# numitron_clock.net
KiCad netlist of a schematic drawn in EAGLE
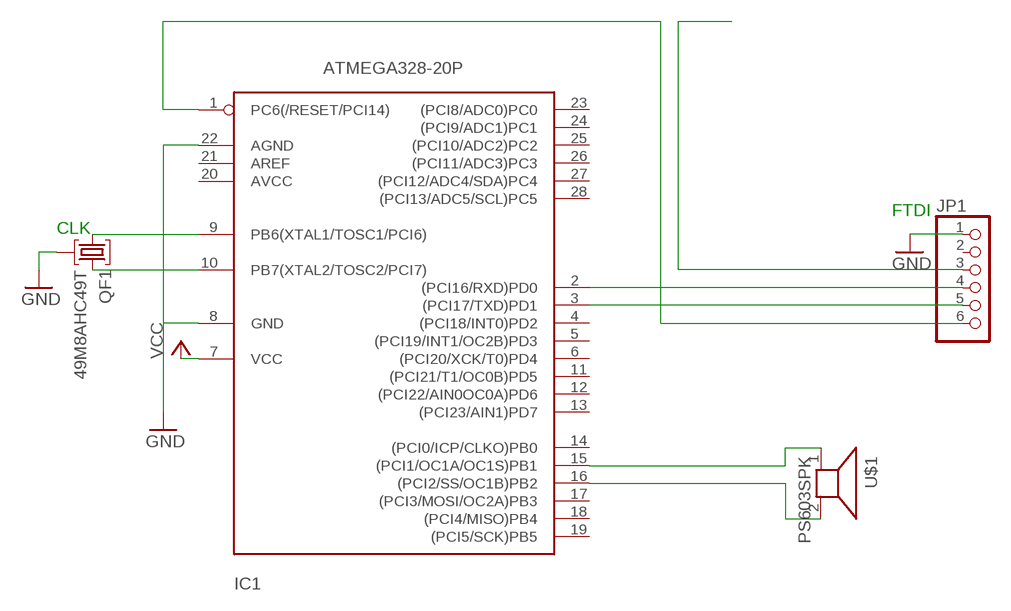
[diagram p0: schematic, sheet 1]

(export (version "E")
  (design (tool "Eeschema 10.0.6"))
  (components
    (comp (ref "IC1")
      (value "ATMEGA328-20P")
      (footprint "eagle-import:DIL28-3")
      (libsource (lib "eagle-import") (part "ATMEGA328P-20"))
    )
    (comp (ref "JP1")
      (value "PINHD-1X6")
      (footprint "eagle-import:1X06")
      (libsource (lib "eagle-import") (part "PINHD-1X6"))
    )
    (comp (ref "QF1")
      (value "49M8AHC49T")
      (footprint "eagle-import:HC49U")
      (libsource (lib "eagle-import") (part "49M8AHC49T"))
    )
    (comp (ref "U$1")
      (value "PS603SPK")
      (footprint "eagle-import:PS603")
      (libsource (lib "eagle-import") (part "PS603SPK"))
    )
  )
  (nets
    (net (code "1") (name "GND") (class "Default")
      (node (ref "IC1") (pin "22") (pinfunction "AGND_22") (pintype "bidirectional"))
      (node (ref "IC1") (pin "8") (pinfunction "GND_8") (pintype "bidirectional"))
      (node (ref "JP1") (pin "1") (pinfunction "1_1") (pintype "passive"))
      (node (ref "QF1") (pin "2") (pinfunction "2_2") (pintype "passive"))
    )
    (net (code "2") (name "Net-(IC1-(PCI1{slash}OC1A{slash}OC1S)PB1)") (class "Default")
      (node (ref "IC1") (pin "15") (pinfunction "(PCI1/OC1A/OC1S)PB1_15") (pintype "bidirectional"))
      (node (ref "U$1") (pin "1") (pinfunction "1_1") (pintype "passive"))
    )
    (net (code "3") (name "Net-(IC1-(PCI2{slash}SS{slash}OC1B)PB2)") (class "Default")
      (node (ref "IC1") (pin "16") (pinfunction "(PCI2/SS/OC1B)PB2_16") (pintype "bidirectional"))
      (node (ref "U$1") (pin "2") (pinfunction "2_2") (pintype "passive"))
    )
    (net (code "4") (name "Net-(IC1-(PCI16{slash}RXD)PD0)") (class "Default")
      (node (ref "IC1") (pin "2") (pinfunction "(PCI16/RXD)PD0_2") (pintype "bidirectional"))
      (node (ref "JP1") (pin "4") (pinfunction "4_4") (pintype "passive"))
    )
    (net (code "5") (name "Net-(IC1-(PCI17{slash}TXD)PD1)") (class "Default")
      (node (ref "IC1") (pin "3") (pinfunction "(PCI17/TXD)PD1_3") (pintype "bidirectional"))
      (node (ref "JP1") (pin "5") (pinfunction "5_5") (pintype "passive"))
    )
    (net (code "6") (name "Net-(IC1-PB6(XTAL1{slash}TOSC1{slash}PCI6))") (class "Default")
      (node (ref "IC1") (pin "9") (pinfunction "PB6(XTAL1/TOSC1/PCI6)_9") (pintype "bidirectional"))
      (node (ref "QF1") (pin "1") (pinfunction "1_1") (pintype "passive"))
    )
    (net (code "7") (name "Net-(IC1-PB7(XTAL2{slash}TOSC2{slash}PCI7))") (class "Default")
      (node (ref "IC1") (pin "10") (pinfunction "PB7(XTAL2/TOSC2/PCI7)_10") (pintype "bidirectional"))
      (node (ref "QF1") (pin "3") (pinfunction "3_3") (pintype "passive"))
    )
    (net (code "8") (name "Net-(IC1-PC6({slash}RESET{slash}PCI14))") (class "Default")
      (node (ref "IC1") (pin "1") (pinfunction "PC6(/RESET/PCI14)_1") (pintype "bidirectional"))
      (node (ref "JP1") (pin "6") (pinfunction "6_6") (pintype "passive"))
    )
    (net (code "9") (name "VCC") (class "Default")
      (node (ref "IC1") (pin "7") (pinfunction "VCC_7") (pintype "bidirectional"))
    )
    (net (code "10") (name "unconnected-(IC1-(PCI0{slash}ICP{slash}CLKO)PB0-Pad14)") (class "Default")
      (node (ref "IC1") (pin "14") (pinfunction "(PCI0/ICP/CLKO)PB0_14") (pintype "bidirectional"))
    )
    (net (code "11") (name "unconnected-(IC1-(PCI3{slash}MOSI{slash}OC2A)PB3-Pad17)") (class "Default")
      (node (ref "IC1") (pin "17") (pinfunction "(PCI3/MOSI/OC2A)PB3_17") (pintype "bidirectional"))
    )
    (net (code "12") (name "unconnected-(IC1-(PCI4{slash}MISO)PB4-Pad18)") (class "Default")
      (node (ref "IC1") (pin "18") (pinfunction "(PCI4/MISO)PB4_18") (pintype "bidirectional"))
    )
    (net (code "13") (name "unconnected-(IC1-(PCI5{slash}SCK)PB5-Pad19)") (class "Default")
      (node (ref "IC1") (pin "19") (pinfunction "(PCI5/SCK)PB5_19") (pintype "bidirectional"))
    )
    (net (code "14") (name "unconnected-(IC1-(PCI8{slash}ADC0)PC0-Pad23)") (class "Default")
      (node (ref "IC1") (pin "23") (pinfunction "(PCI8/ADC0)PC0_23") (pintype "bidirectional"))
    )
    (net (code "15") (name "unconnected-(IC1-(PCI9{slash}ADC1)PC1-Pad24)") (class "Default")
      (node (ref "IC1") (pin "24") (pinfunction "(PCI9/ADC1)PC1_24") (pintype "bidirectional"))
    )
    (net (code "16") (name "unconnected-(IC1-(PCI10{slash}ADC2)PC2-Pad25)") (class "Default")
      (node (ref "IC1") (pin "25") (pinfunction "(PCI10/ADC2)PC2_25") (pintype "bidirectional"))
    )
    (net (code "17") (name "unconnected-(IC1-(PCI11{slash}ADC3)PC3-Pad26)") (class "Default")
      (node (ref "IC1") (pin "26") (pinfunction "(PCI11/ADC3)PC3_26") (pintype "bidirectional"))
    )
    (net (code "18") (name "unconnected-(IC1-(PCI12{slash}ADC4{slash}SDA)PC4-Pad27)") (class "Default")
      (node (ref "IC1") (pin "27") (pinfunction "(PCI12/ADC4/SDA)PC4_27") (pintype "bidirectional"))
    )
    (net (code "19") (name "unconnected-(IC1-(PCI13{slash}ADC5{slash}SCL)PC5-Pad28)") (class "Default")
      (node (ref "IC1") (pin "28") (pinfunction "(PCI13/ADC5/SCL)PC5_28") (pintype "bidirectional"))
    )
    (net (code "20") (name "unconnected-(IC1-(PCI18{slash}INT0)PD2-Pad4)") (class "Default")
      (node (ref "IC1") (pin "4") (pinfunction "(PCI18/INT0)PD2_4") (pintype "bidirectional"))
    )
    (net (code "21") (name "unconnected-(IC1-(PCI19{slash}INT1{slash}OC2B)PD3-Pad5)") (class "Default")
      (node (ref "IC1") (pin "5") (pinfunction "(PCI19/INT1/OC2B)PD3_5") (pintype "bidirectional"))
    )
    (net (code "22") (name "unconnected-(IC1-(PCI20{slash}XCK{slash}T0)PD4-Pad6)") (class "Default")
      (node (ref "IC1") (pin "6") (pinfunction "(PCI20/XCK/T0)PD4_6") (pintype "bidirectional"))
    )
    (net (code "23") (name "unconnected-(IC1-(PCI21{slash}T1{slash}OC0B)PD5-Pad11)") (class "Default")
      (node (ref "IC1") (pin "11") (pinfunction "(PCI21/T1/OC0B)PD5_11") (pintype "bidirectional"))
    )
    (net (code "24") (name "unconnected-(IC1-(PCI22{slash}AIN0OC0A)PD6-Pad12)") (class "Default")
      (node (ref "IC1") (pin "12") (pinfunction "(PCI22/AIN0OC0A)PD6_12") (pintype "bidirectional"))
    )
    (net (code "25") (name "unconnected-(IC1-(PCI23{slash}AIN1)PD7-Pad13)") (class "Default")
      (node (ref "IC1") (pin "13") (pinfunction "(PCI23/AIN1)PD7_13") (pintype "bidirectional"))
    )
    (net (code "26") (name "unconnected-(IC1-AREF-Pad21)") (class "Default")
      (node (ref "IC1") (pin "21") (pinfunction "AREF_21") (pintype "bidirectional"))
    )
    (net (code "27") (name "unconnected-(IC1-AVCC-Pad20)") (class "Default")
      (node (ref "IC1") (pin "20") (pinfunction "AVCC_20") (pintype "bidirectional"))
    )
    (net (code "28") (name "unconnected-(JP1-Pad2)") (class "Default")
      (node (ref "JP1") (pin "2") (pinfunction "2_2") (pintype "passive"))
    )
    (net (code "29") (name "unconnected-(JP1-Pad3)") (class "Default")
      (node (ref "JP1") (pin "3") (pinfunction "3_3") (pintype "passive"))
    )
  )
)
